# I2C_extender_0.net
KiCad netlist of a schematic drawn in Altium Designer
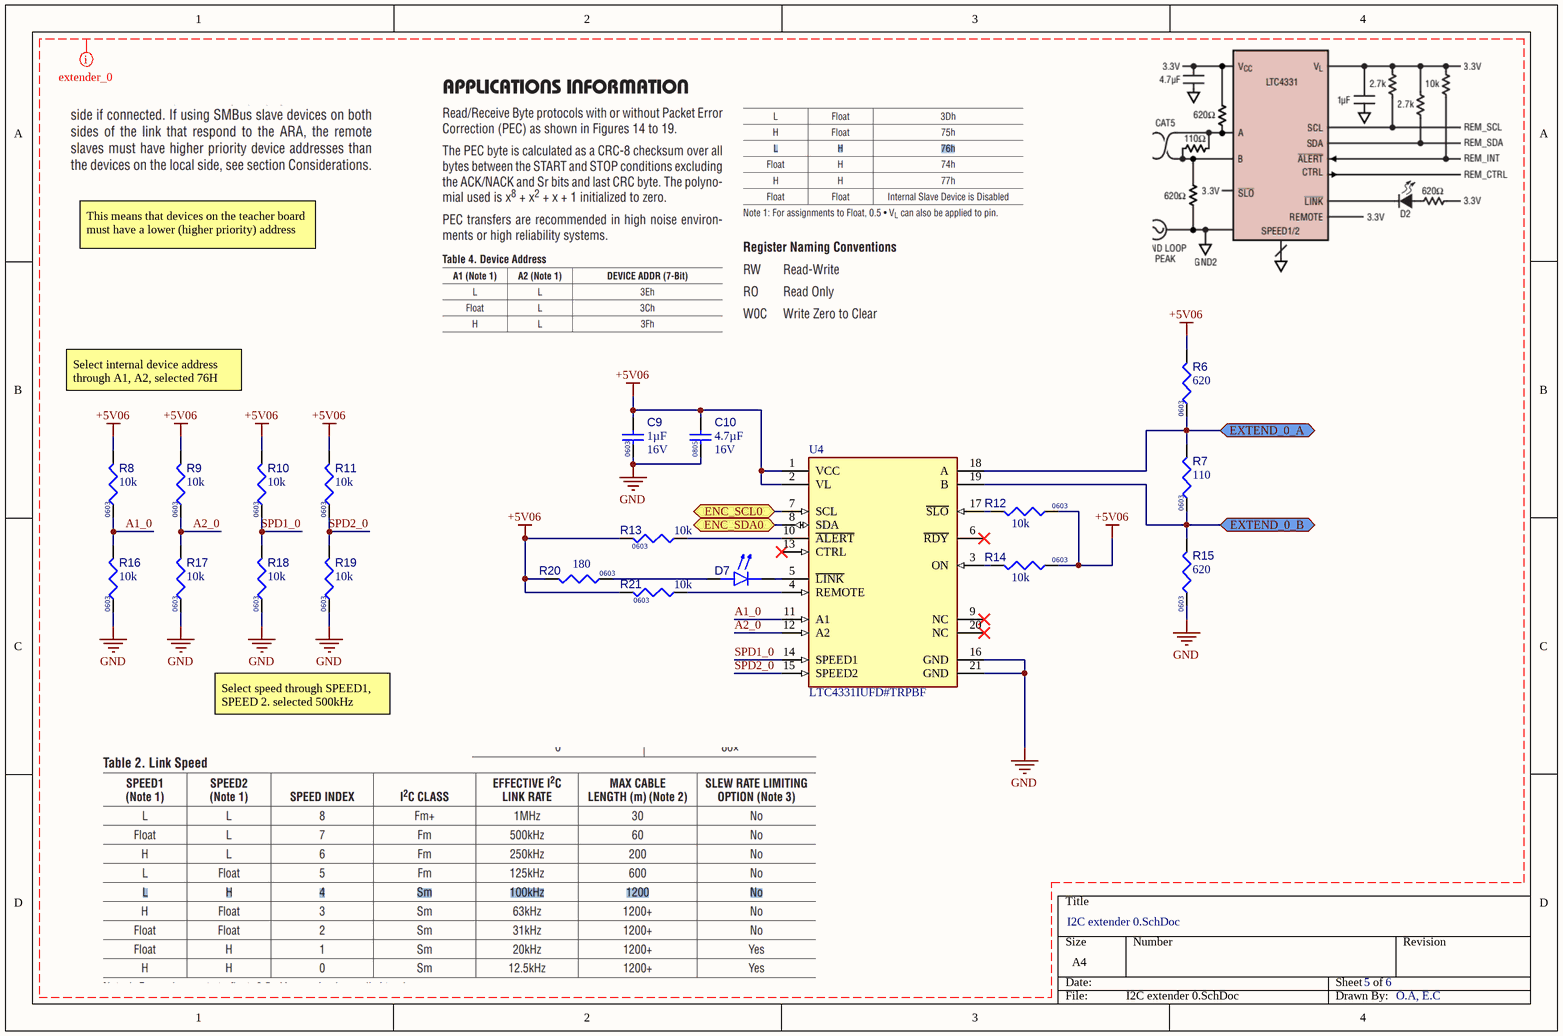
[diagram p0: I2C extender 0.SchDoc]

(export (version "E")
  (design (tool "Eeschema 10.0.6"))
  (components
    (comp (ref "C9")
      (value "1µF")
      (footprint "CAPC1608X90X35NL15T15")
      (description "Chip Capacitor, 1 uF, +/- 10%, 16 V, 0603 (1608 Metric)")
      (fields
        (field (name "CASE/PACKAGE") "0603")
        (field (name "VOLTAGE RATING") "16V")
        (field (name "TOLERANCE") "10%")
        (field (name "Comment") "Capacitor 1uF +/- 10% 16V 0603")
      )
      (libsource (lib "hawaiirobotics") (part "CAP-NP-2"))
    )
    (comp (ref "C10")
      (value "4.7µF")
      (footprint "CL21A475KOFNNNE-Footprint-1")
      (fields
        (field (name "CASE/PACKAGE") "0805")
        (field (name "RATED DC VOLTAGE (URDC)") "16V")
        (field (name "Comment") "CL21A475KOFNNNE")
      )
      (libsource (lib "hawaiirobotics") (part "CAP-NP-2"))
    )
    (comp (ref "D7")
      (value "150060YS75000")
      (footprint "WL-SMCW_0603_150060xx75000")
      (description "Single Color LED, Yellow, Water Clear, 1.1mm")
      (libsource (lib "hawaiirobotics") (part "DIODE-LED-2"))
    )
    (comp (ref "R6")
      (value "620")
      (footprint "RC0603JR-0720KL-Footprint-1")
      (fields
        (field (name "POWER") "100mW")
        (field (name "CASE/PACKAGE") "0603")
        (field (name "TOLERANCE") "1%")
        (field (name "Comment") "RC0603FR-07620RL")
      )
      (libsource (lib "hawaiirobotics") (part "RES-2"))
    )
    (comp (ref "R7")
      (value "110")
      (footprint "RC0603JR-0720KL-Footprint-1")
      (fields
        (field (name "TOLERANCE") "1%")
        (field (name "POWER") "100mW")
        (field (name "CASE/PACKAGE") "0603")
        (field (name "Comment") "RC0603FR-07110RL")
      )
      (libsource (lib "hawaiirobotics") (part "RES-2"))
    )
    (comp (ref "R8")
      (value "10k")
      (footprint "RESC1608X55X25NL10T15")
      (description "Chip Resistor, 10 KOhm, +/- 1%, 01 W, -55 to 155 degC, 0603 (1608 Metric)")
      (fields
        (field (name "CASE/PACKAGE") "0603")
        (field (name "POWER") "100mW")
        (field (name "TOLERANCE") "1%")
      )
      (libsource (lib "hawaiirobotics") (part "RES-2"))
    )
    (comp (ref "R9")
      (value "10k")
      (footprint "RESC1608X55X25NL10T15")
      (description "Chip Resistor, 10 KOhm, +/- 1%, 01 W, -55 to 155 degC, 0603 (1608 Metric)")
      (fields
        (field (name "CASE/PACKAGE") "0603")
        (field (name "POWER") "100mW")
        (field (name "TOLERANCE") "1%")
      )
      (libsource (lib "hawaiirobotics") (part "RES-2"))
    )
    (comp (ref "R10")
      (value "10k")
      (footprint "RESC1608X55X25NL10T15")
      (description "Chip Resistor, 10 KOhm, +/- 1%, 01 W, -55 to 155 degC, 0603 (1608 Metric)")
      (fields
        (field (name "CASE/PACKAGE") "0603")
        (field (name "POWER") "100mW")
        (field (name "TOLERANCE") "1%")
      )
      (libsource (lib "hawaiirobotics") (part "RES-2"))
    )
    (comp (ref "R11")
      (value "10k")
      (footprint "RESC1608X55X25NL10T15")
      (description "Chip Resistor, 10 KOhm, +/- 1%, 01 W, -55 to 155 degC, 0603 (1608 Metric)")
      (fields
        (field (name "CASE/PACKAGE") "0603")
        (field (name "POWER") "100mW")
        (field (name "TOLERANCE") "1%")
      )
      (libsource (lib "hawaiirobotics") (part "RES-2"))
    )
    (comp (ref "R12")
      (value "10k")
      (footprint "RESC1608X55X25NL10T15")
      (description "Chip Resistor, 10 KOhm, +/- 1%, 01 W, -55 to 155 degC, 0603 (1608 Metric)")
      (fields
        (field (name "CASE/PACKAGE") "0603")
        (field (name "POWER") "100mW")
        (field (name "TOLERANCE") "1%")
      )
      (libsource (lib "hawaiirobotics") (part "RES-2"))
    )
    (comp (ref "R13")
      (value "10k")
      (footprint "RESC1608X55X25NL10T15")
      (description "Chip Resistor, 10 KOhm, +/- 1%, 01 W, -55 to 155 degC, 0603 (1608 Metric)")
      (fields
        (field (name "CASE/PACKAGE") "0603")
        (field (name "POWER") "100mW")
        (field (name "TOLERANCE") "1%")
      )
      (libsource (lib "hawaiirobotics") (part "RES-2"))
    )
    (comp (ref "R14")
      (value "10k")
      (footprint "RESC1608X55X25NL10T15")
      (description "Chip Resistor, 10 KOhm, +/- 1%, 01 W, -55 to 155 degC, 0603 (1608 Metric)")
      (fields
        (field (name "CASE/PACKAGE") "0603")
        (field (name "POWER") "100mW")
        (field (name "TOLERANCE") "1%")
      )
      (libsource (lib "hawaiirobotics") (part "RES-2"))
    )
    (comp (ref "R15")
      (value "620")
      (footprint "RC0603JR-0720KL-Footprint-1")
      (fields
        (field (name "POWER") "100mW")
        (field (name "CASE/PACKAGE") "0603")
        (field (name "TOLERANCE") "1%")
        (field (name "Comment") "RC0603FR-07620RL")
      )
      (libsource (lib "hawaiirobotics") (part "RES-2"))
    )
    (comp (ref "R16")
      (value "10k")
      (footprint "RESC1608X55X25NL10T15")
      (description "Chip Resistor, 10 KOhm, +/- 1%, 01 W, -55 to 155 degC, 0603 (1608 Metric)")
      (fields
        (field (name "CASE/PACKAGE") "0603")
        (field (name "POWER") "100mW")
        (field (name "TOLERANCE") "1%")
      )
      (libsource (lib "hawaiirobotics") (part "RES-2"))
    )
    (comp (ref "R17")
      (value "10k")
      (footprint "RESC1608X55X25NL10T15")
      (description "Chip Resistor, 10 KOhm, +/- 1%, 01 W, -55 to 155 degC, 0603 (1608 Metric)")
      (fields
        (field (name "CASE/PACKAGE") "0603")
        (field (name "POWER") "100mW")
        (field (name "TOLERANCE") "1%")
      )
      (libsource (lib "hawaiirobotics") (part "RES-2"))
    )
    (comp (ref "R18")
      (value "10k")
      (footprint "RESC1608X55X25NL10T15")
      (description "Chip Resistor, 10 KOhm, +/- 1%, 01 W, -55 to 155 degC, 0603 (1608 Metric)")
      (fields
        (field (name "CASE/PACKAGE") "0603")
        (field (name "POWER") "100mW")
        (field (name "TOLERANCE") "1%")
      )
      (libsource (lib "hawaiirobotics") (part "RES-2"))
    )
    (comp (ref "R19")
      (value "10k")
      (footprint "RESC1608X55X25NL10T15")
      (description "Chip Resistor, 10 KOhm, +/- 1%, 01 W, -55 to 155 degC, 0603 (1608 Metric)")
      (fields
        (field (name "CASE/PACKAGE") "0603")
        (field (name "POWER") "100mW")
        (field (name "TOLERANCE") "1%")
      )
      (libsource (lib "hawaiirobotics") (part "RES-2"))
    )
    (comp (ref "R20")
      (value "180")
      (footprint "RESC0603(1608)_N")
      (fields
        (field (name "TOLERANCE") "5%")
        (field (name "CASE/PACKAGE") "0603")
        (field (name "POWER") "100mW")
        (field (name "Comment") "RC0603JR-07180RL")
      )
      (libsource (lib "hawaiirobotics") (part "RES-2"))
    )
    (comp (ref "R21")
      (value "10k")
      (footprint "RESC1608X55X25NL10T15")
      (description "Chip Resistor, 10 KOhm, +/- 1%, 01 W, -55 to 155 degC, 0603 (1608 Metric)")
      (fields
        (field (name "CASE/PACKAGE") "0603")
        (field (name "POWER") "100mW")
        (field (name "TOLERANCE") "1%")
      )
      (libsource (lib "hawaiirobotics") (part "RES-2"))
    )
    (comp (ref "U4")
      (value "LTC4331IUFD#TRPBF")
      (footprint "FP-UFD-20-05-08-1711-IPC_C")
      (description "Interface Circuit, CMOS, PQCC20")
      (libsource (lib "hawaiirobotics") (part "90934f5fbb90c4d29cf3ee1665de234"))
    )
  )
  (nets
    (net (code "1") (name "+5V06") (class "Default")
      (node (ref "C10") (pin "2") (pinfunction "2_2") (pintype "passive"))
      (node (ref "C9") (pin "2") (pinfunction "2_2") (pintype "passive"))
      (node (ref "R10") (pin "2") (pinfunction "2_2") (pintype "passive"))
      (node (ref "R11") (pin "2") (pinfunction "2_2") (pintype "passive"))
      (node (ref "R12") (pin "1") (pinfunction "1_1") (pintype "passive"))
      (node (ref "R13") (pin "1") (pinfunction "1_1") (pintype "passive"))
      (node (ref "R14") (pin "1") (pinfunction "1_1") (pintype "passive"))
      (node (ref "R20") (pin "2") (pinfunction "2_2") (pintype "passive"))
      (node (ref "R21") (pin "1") (pinfunction "1_1") (pintype "passive"))
      (node (ref "R6") (pin "2") (pinfunction "2_2") (pintype "passive"))
      (node (ref "R8") (pin "2") (pinfunction "2_2") (pintype "passive"))
      (node (ref "R9") (pin "2") (pinfunction "2_2") (pintype "passive"))
      (node (ref "U4") (pin "1") (pinfunction "VCC_1") (pintype "power_in"))
      (node (ref "U4") (pin "2") (pinfunction "VL_2") (pintype "power_in"))
    )
    (net (code "2") (name "/A1_0") (class "Default")
      (node (ref "R16") (pin "2") (pinfunction "2_2") (pintype "passive"))
      (node (ref "R8") (pin "1") (pinfunction "1_1") (pintype "passive"))
      (node (ref "U4") (pin "11") (pinfunction "A1_11") (pintype "input"))
    )
    (net (code "3") (name "/A2_0") (class "Default")
      (node (ref "R17") (pin "2") (pinfunction "2_2") (pintype "passive"))
      (node (ref "R9") (pin "1") (pinfunction "1_1") (pintype "passive"))
      (node (ref "U4") (pin "12") (pinfunction "A2_12") (pintype "input"))
    )
    (net (code "4") (name "/ENC_SCL0") (class "Default")
      (node (ref "U4") (pin "7") (pinfunction "SCL_7") (pintype "input"))
    )
    (net (code "5") (name "/ENC_SDA0") (class "Default")
      (node (ref "U4") (pin "8") (pinfunction "SDA_8") (pintype "bidirectional"))
    )
    (net (code "6") (name "/EXTEND_0_A") (class "Default")
      (node (ref "R6") (pin "1") (pinfunction "1_1") (pintype "passive"))
      (node (ref "R7") (pin "2") (pinfunction "2_2") (pintype "passive"))
      (node (ref "U4") (pin "18") (pinfunction "A_18") (pintype "tri_state"))
    )
    (net (code "7") (name "/EXTEND_0_B") (class "Default")
      (node (ref "R15") (pin "2") (pinfunction "2_2") (pintype "passive"))
      (node (ref "R7") (pin "1") (pinfunction "1_1") (pintype "passive"))
      (node (ref "U4") (pin "19") (pinfunction "B_19") (pintype "tri_state"))
    )
    (net (code "8") (name "/SPD1_0") (class "Default")
      (node (ref "R10") (pin "1") (pinfunction "1_1") (pintype "passive"))
      (node (ref "R18") (pin "2") (pinfunction "2_2") (pintype "passive"))
      (node (ref "U4") (pin "14") (pinfunction "SPEED1_14") (pintype "input"))
    )
    (net (code "9") (name "/SPD2_0") (class "Default")
      (node (ref "R11") (pin "1") (pinfunction "1_1") (pintype "passive"))
      (node (ref "R19") (pin "2") (pinfunction "2_2") (pintype "passive"))
      (node (ref "U4") (pin "15") (pinfunction "SPEED2_15") (pintype "input"))
    )
    (net (code "10") (name "GND") (class "Default")
      (node (ref "C10") (pin "1") (pinfunction "1_1") (pintype "passive"))
      (node (ref "C9") (pin "1") (pinfunction "1_1") (pintype "passive"))
      (node (ref "R15") (pin "1") (pinfunction "1_1") (pintype "passive"))
      (node (ref "R16") (pin "1") (pinfunction "1_1") (pintype "passive"))
      (node (ref "R17") (pin "1") (pinfunction "1_1") (pintype "passive"))
      (node (ref "R18") (pin "1") (pinfunction "1_1") (pintype "passive"))
      (node (ref "R19") (pin "1") (pinfunction "1_1") (pintype "passive"))
      (node (ref "U4") (pin "16") (pinfunction "GND_16") (pintype "power_in"))
      (node (ref "U4") (pin "21") (pinfunction "GND_21") (pintype "power_in"))
    )
    (net (code "11") (name "Net-(D7-A)") (class "Default")
      (node (ref "D7") (pin "2") (pinfunction "A_2") (pintype "passive"))
      (node (ref "R20") (pin "1") (pinfunction "1_1") (pintype "passive"))
    )
    (net (code "12") (name "Net-(D7-K)") (class "Default")
      (node (ref "D7") (pin "1") (pinfunction "K_1") (pintype "passive"))
      (node (ref "U4") (pin "5") (pinfunction "~{LINK}_5") (pintype "open_collector"))
    )
    (net (code "13") (name "Net-(U4-ON)") (class "Default")
      (node (ref "R14") (pin "2") (pinfunction "2_2") (pintype "passive"))
      (node (ref "U4") (pin "3") (pinfunction "ON_3") (pintype "input"))
    )
    (net (code "14") (name "Net-(U4-REMOTE)") (class "Default")
      (node (ref "R21") (pin "2") (pinfunction "2_2") (pintype "passive"))
      (node (ref "U4") (pin "4") (pinfunction "REMOTE_4") (pintype "input"))
    )
    (net (code "15") (name "Net-(U4-~{ALERT})") (class "Default")
      (node (ref "R13") (pin "2") (pinfunction "2_2") (pintype "passive"))
      (node (ref "U4") (pin "10") (pinfunction "~{ALERT}_10") (pintype "open_collector"))
    )
    (net (code "16") (name "Net-(U4-~{SLO})") (class "Default")
      (node (ref "R12") (pin "2") (pinfunction "2_2") (pintype "passive"))
      (node (ref "U4") (pin "17") (pinfunction "~{SLO}_17") (pintype "input"))
    )
    (net (code "17") (name "unconnected-(U4-CTRL-Pad13)") (class "Default")
      (node (ref "U4") (pin "13") (pinfunction "CTRL_13") (pintype "input+no_connect"))
    )
    (net (code "18") (name "unconnected-(U4-NC-Pad9)") (class "Default")
      (node (ref "U4") (pin "9") (pinfunction "NC_9") (pintype "passive+no_connect"))
    )
    (net (code "19") (name "unconnected-(U4-NC-Pad20)") (class "Default")
      (node (ref "U4") (pin "20") (pinfunction "NC_20") (pintype "passive+no_connect"))
    )
    (net (code "20") (name "unconnected-(U4-~{RDY}-Pad6)") (class "Default")
      (node (ref "U4") (pin "6") (pinfunction "~{RDY}_6") (pintype "open_collector+no_connect"))
    )
  )
)
